# canable.net
KiCad netlist of a schematic drawn in EAGLE
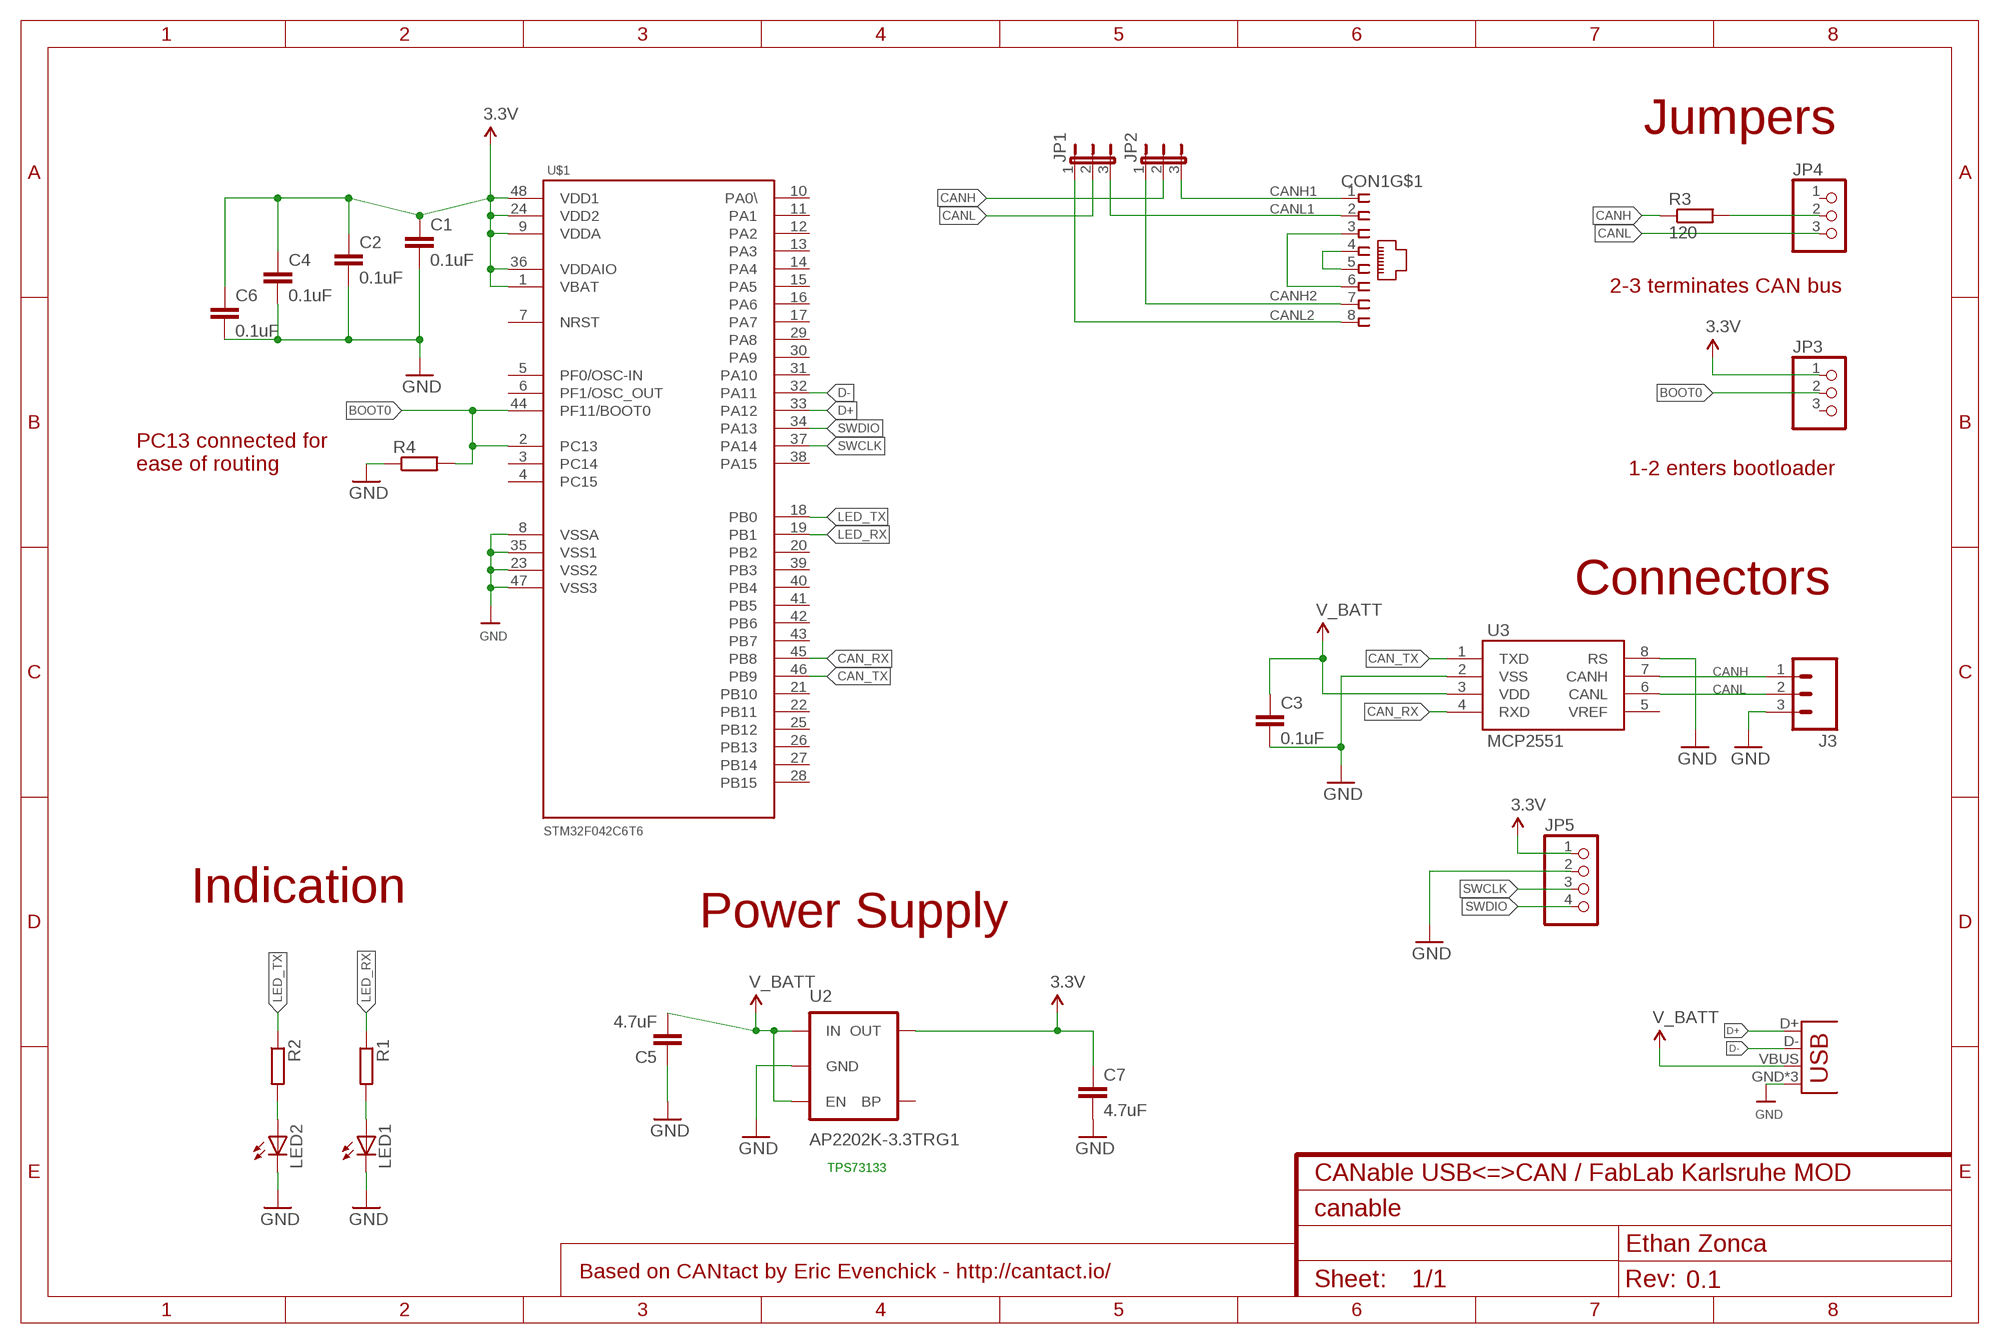
[diagram p0: schematic, sheet 1]

(export (version "E")
  (design (tool "Eeschema 10.0.6"))
  (components
    (comp (ref "C1")
      (value "0.1uF")
      (footprint "eagle-import:C0805")
      (libsource (lib "eagle-import") (part "C-EUC0805"))
    )
    (comp (ref "C2")
      (value "0.1uF")
      (footprint "eagle-import:C0805")
      (libsource (lib "eagle-import") (part "C-EUC0805"))
    )
    (comp (ref "C3")
      (value "0.1uF")
      (footprint "eagle-import:C0805")
      (libsource (lib "eagle-import") (part "C-EUC0805"))
    )
    (comp (ref "C4")
      (value "0.1uF")
      (footprint "eagle-import:C0805")
      (libsource (lib "eagle-import") (part "C-EUC0805"))
    )
    (comp (ref "C5")
      (value "4.7uF")
      (footprint "eagle-import:C0805")
      (libsource (lib "eagle-import") (part "C-EUC0805"))
    )
    (comp (ref "C6")
      (value "0.1uF")
      (footprint "eagle-import:C0805")
      (libsource (lib "eagle-import") (part "C-EUC0805"))
    )
    (comp (ref "C7")
      (value "4.7uF")
      (footprint "eagle-import:C0805")
      (libsource (lib "eagle-import") (part "C-EUC0805"))
    )
    (comp (ref "CON1")
      (value "MEBP_8-8G")
      (footprint "eagle-import:MEBP")
      (libsource (lib "eagle-import") (part "MEBP_8-8G"))
    )
    (comp (ref "J2")
      (value "USB-MICROB")
      (footprint "eagle-import:USB-MICROB")
      (libsource (lib "eagle-import") (part "USB-MICROB"))
    )
    (comp (ref "J3")
      (value "M03SCREW_LOCK")
      (footprint "eagle-import:SCREWTERMINAL-3.5MM-3_LOCK.007S")
      (libsource (lib "eagle-import") (part "M03SCREW_LOCK"))
    )
    (comp (ref "JP1")
      (value "JP2E")
      (footprint "eagle-import:JP2")
      (libsource (lib "eagle-import") (part "JP2E"))
    )
    (comp (ref "JP2")
      (value "JP2E")
      (footprint "eagle-import:JP2")
      (libsource (lib "eagle-import") (part "JP2E"))
    )
    (comp (ref "JP3")
      (value "PINHD-1X3")
      (footprint "eagle-import:1X03")
      (libsource (lib "eagle-import") (part "PINHD-1X3"))
    )
    (comp (ref "JP4")
      (value "PINHD-1X3")
      (footprint "eagle-import:1X03")
      (libsource (lib "eagle-import") (part "PINHD-1X3"))
    )
    (comp (ref "JP5")
      (value "PINHD-1X4")
      (footprint "eagle-import:1X04")
      (libsource (lib "eagle-import") (part "PINHD-1X4"))
    )
    (comp (ref "LED1")
      (value "LEDCHIPLED_1206")
      (footprint "eagle-import:CHIPLED_1206")
      (libsource (lib "eagle-import") (part "LEDCHIPLED_1206"))
    )
    (comp (ref "LED2")
      (value "LEDCHIPLED_1206")
      (footprint "eagle-import:CHIPLED_1206")
      (libsource (lib "eagle-import") (part "LEDCHIPLED_1206"))
    )
    (comp (ref "R1")
      (value "R-EU_R0805")
      (footprint "eagle-import:R0805")
      (libsource (lib "eagle-import") (part "R-EU_R0805"))
    )
    (comp (ref "R2")
      (value "R-EU_R0805")
      (footprint "eagle-import:R0805")
      (libsource (lib "eagle-import") (part "R-EU_R0805"))
    )
    (comp (ref "R3")
      (value "120")
      (footprint "eagle-import:R0805")
      (libsource (lib "eagle-import") (part "R-EU_R0805"))
    )
    (comp (ref "R4")
      (value "R-EU_R0805")
      (footprint "eagle-import:R0805")
      (libsource (lib "eagle-import") (part "R-EU_R0805"))
    )
    (comp (ref "U$1")
      (value "STM32F042C6T6")
      (footprint "eagle-import:LQFP48")
      (libsource (lib "eagle-import") (part "STM32F042C6T6"))
    )
    (comp (ref "U2")
      (value "AP2202K-3.3TRG1")
      (footprint "eagle-import:SOT23-5")
      (libsource (lib "eagle-import") (part "MIC52053.3V"))
    )
    (comp (ref "U3")
      (value "MCP2551")
      (footprint "eagle-import:SO08")
      (libsource (lib "eagle-import") (part "MCP2551"))
    )
  )
  (nets
    (net (code "1") (name "/CANH1") (class "Default")
      (node (ref "CON1") (pin "1") (pinfunction "1_1") (pintype "passive"))
      (node (ref "JP2") (pin "3") (pinfunction "3_3") (pintype "passive"))
    )
    (net (code "2") (name "/CANH2") (class "Default")
      (node (ref "CON1") (pin "7") (pinfunction "7_7") (pintype "passive"))
      (node (ref "JP2") (pin "1") (pinfunction "1_1") (pintype "passive"))
    )
    (net (code "3") (name "/CANL1") (class "Default")
      (node (ref "CON1") (pin "2") (pinfunction "2_2") (pintype "passive"))
      (node (ref "JP1") (pin "3") (pinfunction "3_3") (pintype "passive"))
    )
    (net (code "4") (name "/CANL2") (class "Default")
      (node (ref "CON1") (pin "8") (pinfunction "8_8") (pintype "passive"))
      (node (ref "JP1") (pin "1") (pinfunction "1_1") (pintype "passive"))
    )
    (net (code "5") (name "3.3V") (class "Default")
      (node (ref "C1") (pin "1") (pinfunction "1_1") (pintype "passive"))
      (node (ref "C2") (pin "1") (pinfunction "1_1") (pintype "passive"))
      (node (ref "C4") (pin "1") (pinfunction "1_1") (pintype "passive"))
      (node (ref "C6") (pin "1") (pinfunction "1_1") (pintype "passive"))
      (node (ref "C7") (pin "1") (pinfunction "1_1") (pintype "passive"))
      (node (ref "JP3") (pin "1") (pinfunction "1_1") (pintype "passive"))
      (node (ref "JP5") (pin "1") (pinfunction "1_1") (pintype "passive"))
      (node (ref "U$1") (pin "1") (pinfunction "VBAT_1") (pintype "bidirectional"))
      (node (ref "U$1") (pin "24") (pinfunction "VDD2_24") (pintype "bidirectional"))
      (node (ref "U$1") (pin "36") (pinfunction "VDDAIO_36") (pintype "bidirectional"))
      (node (ref "U$1") (pin "48") (pinfunction "VDD1_48") (pintype "bidirectional"))
      (node (ref "U$1") (pin "9") (pinfunction "VDDA_9") (pintype "bidirectional"))
      (node (ref "U2") (pin "5") (pinfunction "OUT_5") (pintype "passive"))
    )
    (net (code "6") (name "BOOT0") (class "Default")
      (node (ref "JP3") (pin "2") (pinfunction "2_2") (pintype "passive"))
      (node (ref "R4") (pin "2") (pinfunction "2_2") (pintype "passive"))
      (node (ref "U$1") (pin "2") (pinfunction "PC13_2") (pintype "bidirectional"))
      (node (ref "U$1") (pin "44") (pinfunction "PF11/BOOT0_44") (pintype "bidirectional"))
    )
    (net (code "7") (name "CANH") (class "Default")
      (node (ref "J3") (pin "1") (pinfunction "1_1") (pintype "passive"))
      (node (ref "JP2") (pin "2") (pinfunction "2_2") (pintype "passive"))
      (node (ref "R3") (pin "1") (pinfunction "1_1") (pintype "passive"))
      (node (ref "U3") (pin "7") (pinfunction "CANH_7") (pintype "bidirectional"))
    )
    (net (code "8") (name "CANL") (class "Default")
      (node (ref "J3") (pin "2") (pinfunction "2_2") (pintype "passive"))
      (node (ref "JP1") (pin "2") (pinfunction "2_2") (pintype "passive"))
      (node (ref "JP4") (pin "3") (pinfunction "3_3") (pintype "passive"))
      (node (ref "U3") (pin "6") (pinfunction "CANL_6") (pintype "bidirectional"))
    )
    (net (code "9") (name "CAN_RX") (class "Default")
      (node (ref "U$1") (pin "45") (pinfunction "PB8_45") (pintype "bidirectional"))
      (node (ref "U3") (pin "4") (pinfunction "RXD_4") (pintype "bidirectional"))
    )
    (net (code "10") (name "CAN_TX") (class "Default")
      (node (ref "U$1") (pin "46") (pinfunction "PB9_46") (pintype "bidirectional"))
      (node (ref "U3") (pin "1") (pinfunction "TXD_1") (pintype "bidirectional"))
    )
    (net (code "11") (name "D+") (class "Default")
      (node (ref "J2") (pin "D+") (pinfunction "D+_D+") (pintype "bidirectional"))
      (node (ref "U$1") (pin "33") (pinfunction "PA12_33") (pintype "bidirectional"))
    )
    (net (code "12") (name "D-") (class "Default")
      (node (ref "J2") (pin "D-") (pinfunction "D-_D-") (pintype "bidirectional"))
      (node (ref "U$1") (pin "32") (pinfunction "PA11_32") (pintype "bidirectional"))
    )
    (net (code "13") (name "GND") (class "Default")
      (node (ref "C1") (pin "2") (pinfunction "2_2") (pintype "passive"))
      (node (ref "C2") (pin "2") (pinfunction "2_2") (pintype "passive"))
      (node (ref "C3") (pin "2") (pinfunction "2_2") (pintype "passive"))
      (node (ref "C4") (pin "2") (pinfunction "2_2") (pintype "passive"))
      (node (ref "C5") (pin "1") (pinfunction "1_1") (pintype "passive"))
      (node (ref "C6") (pin "2") (pinfunction "2_2") (pintype "passive"))
      (node (ref "C7") (pin "2") (pinfunction "2_2") (pintype "passive"))
      (node (ref "J2") (pin "GND") (pinfunction "GND_GND") (pintype "bidirectional"))
      (node (ref "J2") (pin "MT1") (pinfunction "GND_MT1") (pintype "bidirectional"))
      (node (ref "J2") (pin "MT2") (pinfunction "GND_MT2") (pintype "bidirectional"))
      (node (ref "J3") (pin "3") (pinfunction "3_3") (pintype "passive"))
      (node (ref "JP5") (pin "2") (pinfunction "2_2") (pintype "passive"))
      (node (ref "LED1") (pin "C") (pinfunction "C_C") (pintype "passive"))
      (node (ref "LED2") (pin "C") (pinfunction "C_C") (pintype "passive"))
      (node (ref "R4") (pin "1") (pinfunction "1_1") (pintype "passive"))
      (node (ref "U$1") (pin "23") (pinfunction "VSS2_23") (pintype "bidirectional"))
      (node (ref "U$1") (pin "35") (pinfunction "VSS1_35") (pintype "bidirectional"))
      (node (ref "U$1") (pin "47") (pinfunction "VSS3_47") (pintype "bidirectional"))
      (node (ref "U$1") (pin "8") (pinfunction "VSSA_8") (pintype "bidirectional"))
      (node (ref "U2") (pin "2") (pinfunction "GND_2") (pintype "input"))
      (node (ref "U3") (pin "2") (pinfunction "VSS_2") (pintype "bidirectional"))
      (node (ref "U3") (pin "8") (pinfunction "RS_8") (pintype "bidirectional"))
    )
    (net (code "14") (name "LED_RX") (class "Default")
      (node (ref "R1") (pin "1") (pinfunction "1_1") (pintype "passive"))
      (node (ref "U$1") (pin "19") (pinfunction "PB1_19") (pintype "bidirectional"))
    )
    (net (code "15") (name "LED_TX") (class "Default")
      (node (ref "R2") (pin "1") (pinfunction "1_1") (pintype "passive"))
      (node (ref "U$1") (pin "18") (pinfunction "PB0_18") (pintype "bidirectional"))
    )
    (net (code "16") (name "Net-(CON1-Pad3)") (class "Default")
      (node (ref "CON1") (pin "3") (pinfunction "3_3") (pintype "passive"))
      (node (ref "CON1") (pin "6") (pinfunction "6_6") (pintype "passive"))
    )
    (net (code "17") (name "Net-(CON1-Pad4)") (class "Default")
      (node (ref "CON1") (pin "4") (pinfunction "4_4") (pintype "passive"))
      (node (ref "CON1") (pin "5") (pinfunction "5_5") (pintype "passive"))
    )
    (net (code "18") (name "Net-(JP4-Pad2)") (class "Default")
      (node (ref "JP4") (pin "2") (pinfunction "2_2") (pintype "passive"))
      (node (ref "R3") (pin "2") (pinfunction "2_2") (pintype "passive"))
    )
    (net (code "19") (name "Net-(LED1-PadA)") (class "Default")
      (node (ref "LED1") (pin "A") (pinfunction "A_A") (pintype "passive"))
      (node (ref "R1") (pin "2") (pinfunction "2_2") (pintype "passive"))
    )
    (net (code "20") (name "Net-(LED2-PadA)") (class "Default")
      (node (ref "LED2") (pin "A") (pinfunction "A_A") (pintype "passive"))
      (node (ref "R2") (pin "2") (pinfunction "2_2") (pintype "passive"))
    )
    (net (code "21") (name "SWCLK") (class "Default")
      (node (ref "JP5") (pin "3") (pinfunction "3_3") (pintype "passive"))
      (node (ref "U$1") (pin "37") (pinfunction "PA14_37") (pintype "bidirectional"))
    )
    (net (code "22") (name "SWDIO") (class "Default")
      (node (ref "JP5") (pin "4") (pinfunction "4_4") (pintype "passive"))
      (node (ref "U$1") (pin "34") (pinfunction "PA13_34") (pintype "bidirectional"))
    )
    (net (code "23") (name "V_BATT") (class "Default")
      (node (ref "C3") (pin "1") (pinfunction "1_1") (pintype "passive"))
      (node (ref "C5") (pin "2") (pinfunction "2_2") (pintype "passive"))
      (node (ref "J2") (pin "VBUS") (pinfunction "VBUS_VBUS") (pintype "bidirectional"))
      (node (ref "U2") (pin "1") (pinfunction "IN_1") (pintype "input"))
      (node (ref "U2") (pin "3") (pinfunction "EN_3") (pintype "input"))
      (node (ref "U3") (pin "3") (pinfunction "VDD_3") (pintype "bidirectional"))
    )
    (net (code "24") (name "unconnected-(JP3-Pad3)") (class "Default")
      (node (ref "JP3") (pin "3") (pinfunction "3_3") (pintype "passive"))
    )
    (net (code "25") (name "unconnected-(JP4-Pad1)") (class "Default")
      (node (ref "JP4") (pin "1") (pinfunction "1_1") (pintype "passive"))
    )
    (net (code "26") (name "unconnected-(U$1-NRST-Pad7)") (class "Default")
      (node (ref "U$1") (pin "7") (pinfunction "NRST_7") (pintype "bidirectional"))
    )
    (net (code "27") (name "unconnected-(U$1-PA0\\-Pad10)") (class "Default")
      (node (ref "U$1") (pin "10") (pinfunction "PA0\\_10") (pintype "bidirectional"))
    )
    (net (code "28") (name "unconnected-(U$1-PA1-Pad11)") (class "Default")
      (node (ref "U$1") (pin "11") (pinfunction "PA1_11") (pintype "bidirectional"))
    )
    (net (code "29") (name "unconnected-(U$1-PA2-Pad12)") (class "Default")
      (node (ref "U$1") (pin "12") (pinfunction "PA2_12") (pintype "bidirectional"))
    )
    (net (code "30") (name "unconnected-(U$1-PA3-Pad13)") (class "Default")
      (node (ref "U$1") (pin "13") (pinfunction "PA3_13") (pintype "bidirectional"))
    )
    (net (code "31") (name "unconnected-(U$1-PA4-Pad14)") (class "Default")
      (node (ref "U$1") (pin "14") (pinfunction "PA4_14") (pintype "bidirectional"))
    )
    (net (code "32") (name "unconnected-(U$1-PA5-Pad15)") (class "Default")
      (node (ref "U$1") (pin "15") (pinfunction "PA5_15") (pintype "bidirectional"))
    )
    (net (code "33") (name "unconnected-(U$1-PA6-Pad16)") (class "Default")
      (node (ref "U$1") (pin "16") (pinfunction "PA6_16") (pintype "bidirectional"))
    )
    (net (code "34") (name "unconnected-(U$1-PA7-Pad17)") (class "Default")
      (node (ref "U$1") (pin "17") (pinfunction "PA7_17") (pintype "bidirectional"))
    )
    (net (code "35") (name "unconnected-(U$1-PA8-Pad29)") (class "Default")
      (node (ref "U$1") (pin "29") (pinfunction "PA8_29") (pintype "bidirectional"))
    )
    (net (code "36") (name "unconnected-(U$1-PA9-Pad30)") (class "Default")
      (node (ref "U$1") (pin "30") (pinfunction "PA9_30") (pintype "bidirectional"))
    )
    (net (code "37") (name "unconnected-(U$1-PA10-Pad31)") (class "Default")
      (node (ref "U$1") (pin "31") (pinfunction "PA10_31") (pintype "bidirectional"))
    )
    (net (code "38") (name "unconnected-(U$1-PA15-Pad38)") (class "Default")
      (node (ref "U$1") (pin "38") (pinfunction "PA15_38") (pintype "bidirectional"))
    )
    (net (code "39") (name "unconnected-(U$1-PB2-Pad20)") (class "Default")
      (node (ref "U$1") (pin "20") (pinfunction "PB2_20") (pintype "bidirectional"))
    )
    (net (code "40") (name "unconnected-(U$1-PB3-Pad39)") (class "Default")
      (node (ref "U$1") (pin "39") (pinfunction "PB3_39") (pintype "bidirectional"))
    )
    (net (code "41") (name "unconnected-(U$1-PB4-Pad40)") (class "Default")
      (node (ref "U$1") (pin "40") (pinfunction "PB4_40") (pintype "bidirectional"))
    )
    (net (code "42") (name "unconnected-(U$1-PB5-Pad41)") (class "Default")
      (node (ref "U$1") (pin "41") (pinfunction "PB5_41") (pintype "bidirectional"))
    )
    (net (code "43") (name "unconnected-(U$1-PB6-Pad42)") (class "Default")
      (node (ref "U$1") (pin "42") (pinfunction "PB6_42") (pintype "bidirectional"))
    )
    (net (code "44") (name "unconnected-(U$1-PB7-Pad43)") (class "Default")
      (node (ref "U$1") (pin "43") (pinfunction "PB7_43") (pintype "bidirectional"))
    )
    (net (code "45") (name "unconnected-(U$1-PB10-Pad21)") (class "Default")
      (node (ref "U$1") (pin "21") (pinfunction "PB10_21") (pintype "bidirectional"))
    )
    (net (code "46") (name "unconnected-(U$1-PB11-Pad22)") (class "Default")
      (node (ref "U$1") (pin "22") (pinfunction "PB11_22") (pintype "bidirectional"))
    )
    (net (code "47") (name "unconnected-(U$1-PB12-Pad25)") (class "Default")
      (node (ref "U$1") (pin "25") (pinfunction "PB12_25") (pintype "bidirectional"))
    )
    (net (code "48") (name "unconnected-(U$1-PB13-Pad26)") (class "Default")
      (node (ref "U$1") (pin "26") (pinfunction "PB13_26") (pintype "bidirectional"))
    )
    (net (code "49") (name "unconnected-(U$1-PB14-Pad27)") (class "Default")
      (node (ref "U$1") (pin "27") (pinfunction "PB14_27") (pintype "bidirectional"))
    )
    (net (code "50") (name "unconnected-(U$1-PB15-Pad28)") (class "Default")
      (node (ref "U$1") (pin "28") (pinfunction "PB15_28") (pintype "bidirectional"))
    )
    (net (code "51") (name "unconnected-(U$1-PC14-Pad3)") (class "Default")
      (node (ref "U$1") (pin "3") (pinfunction "PC14_3") (pintype "bidirectional"))
    )
    (net (code "52") (name "unconnected-(U$1-PC15-Pad4)") (class "Default")
      (node (ref "U$1") (pin "4") (pinfunction "PC15_4") (pintype "bidirectional"))
    )
    (net (code "53") (name "unconnected-(U$1-PF0{slash}OSC-IN-Pad5)") (class "Default")
      (node (ref "U$1") (pin "5") (pinfunction "PF0/OSC-IN_5") (pintype "bidirectional"))
    )
    (net (code "54") (name "unconnected-(U$1-PF1{slash}OSC_OUT-Pad6)") (class "Default")
      (node (ref "U$1") (pin "6") (pinfunction "PF1/OSC_OUT_6") (pintype "bidirectional"))
    )
    (net (code "55") (name "unconnected-(U2-BP-Pad4)") (class "Default")
      (node (ref "U2") (pin "4") (pinfunction "BP_4") (pintype "input"))
    )
    (net (code "56") (name "unconnected-(U3-VREF-Pad5)") (class "Default")
      (node (ref "U3") (pin "5") (pinfunction "VREF_5") (pintype "bidirectional"))
    )
  )
)
